# video_board.net
KiCad netlist of a schematic drawn in EAGLE
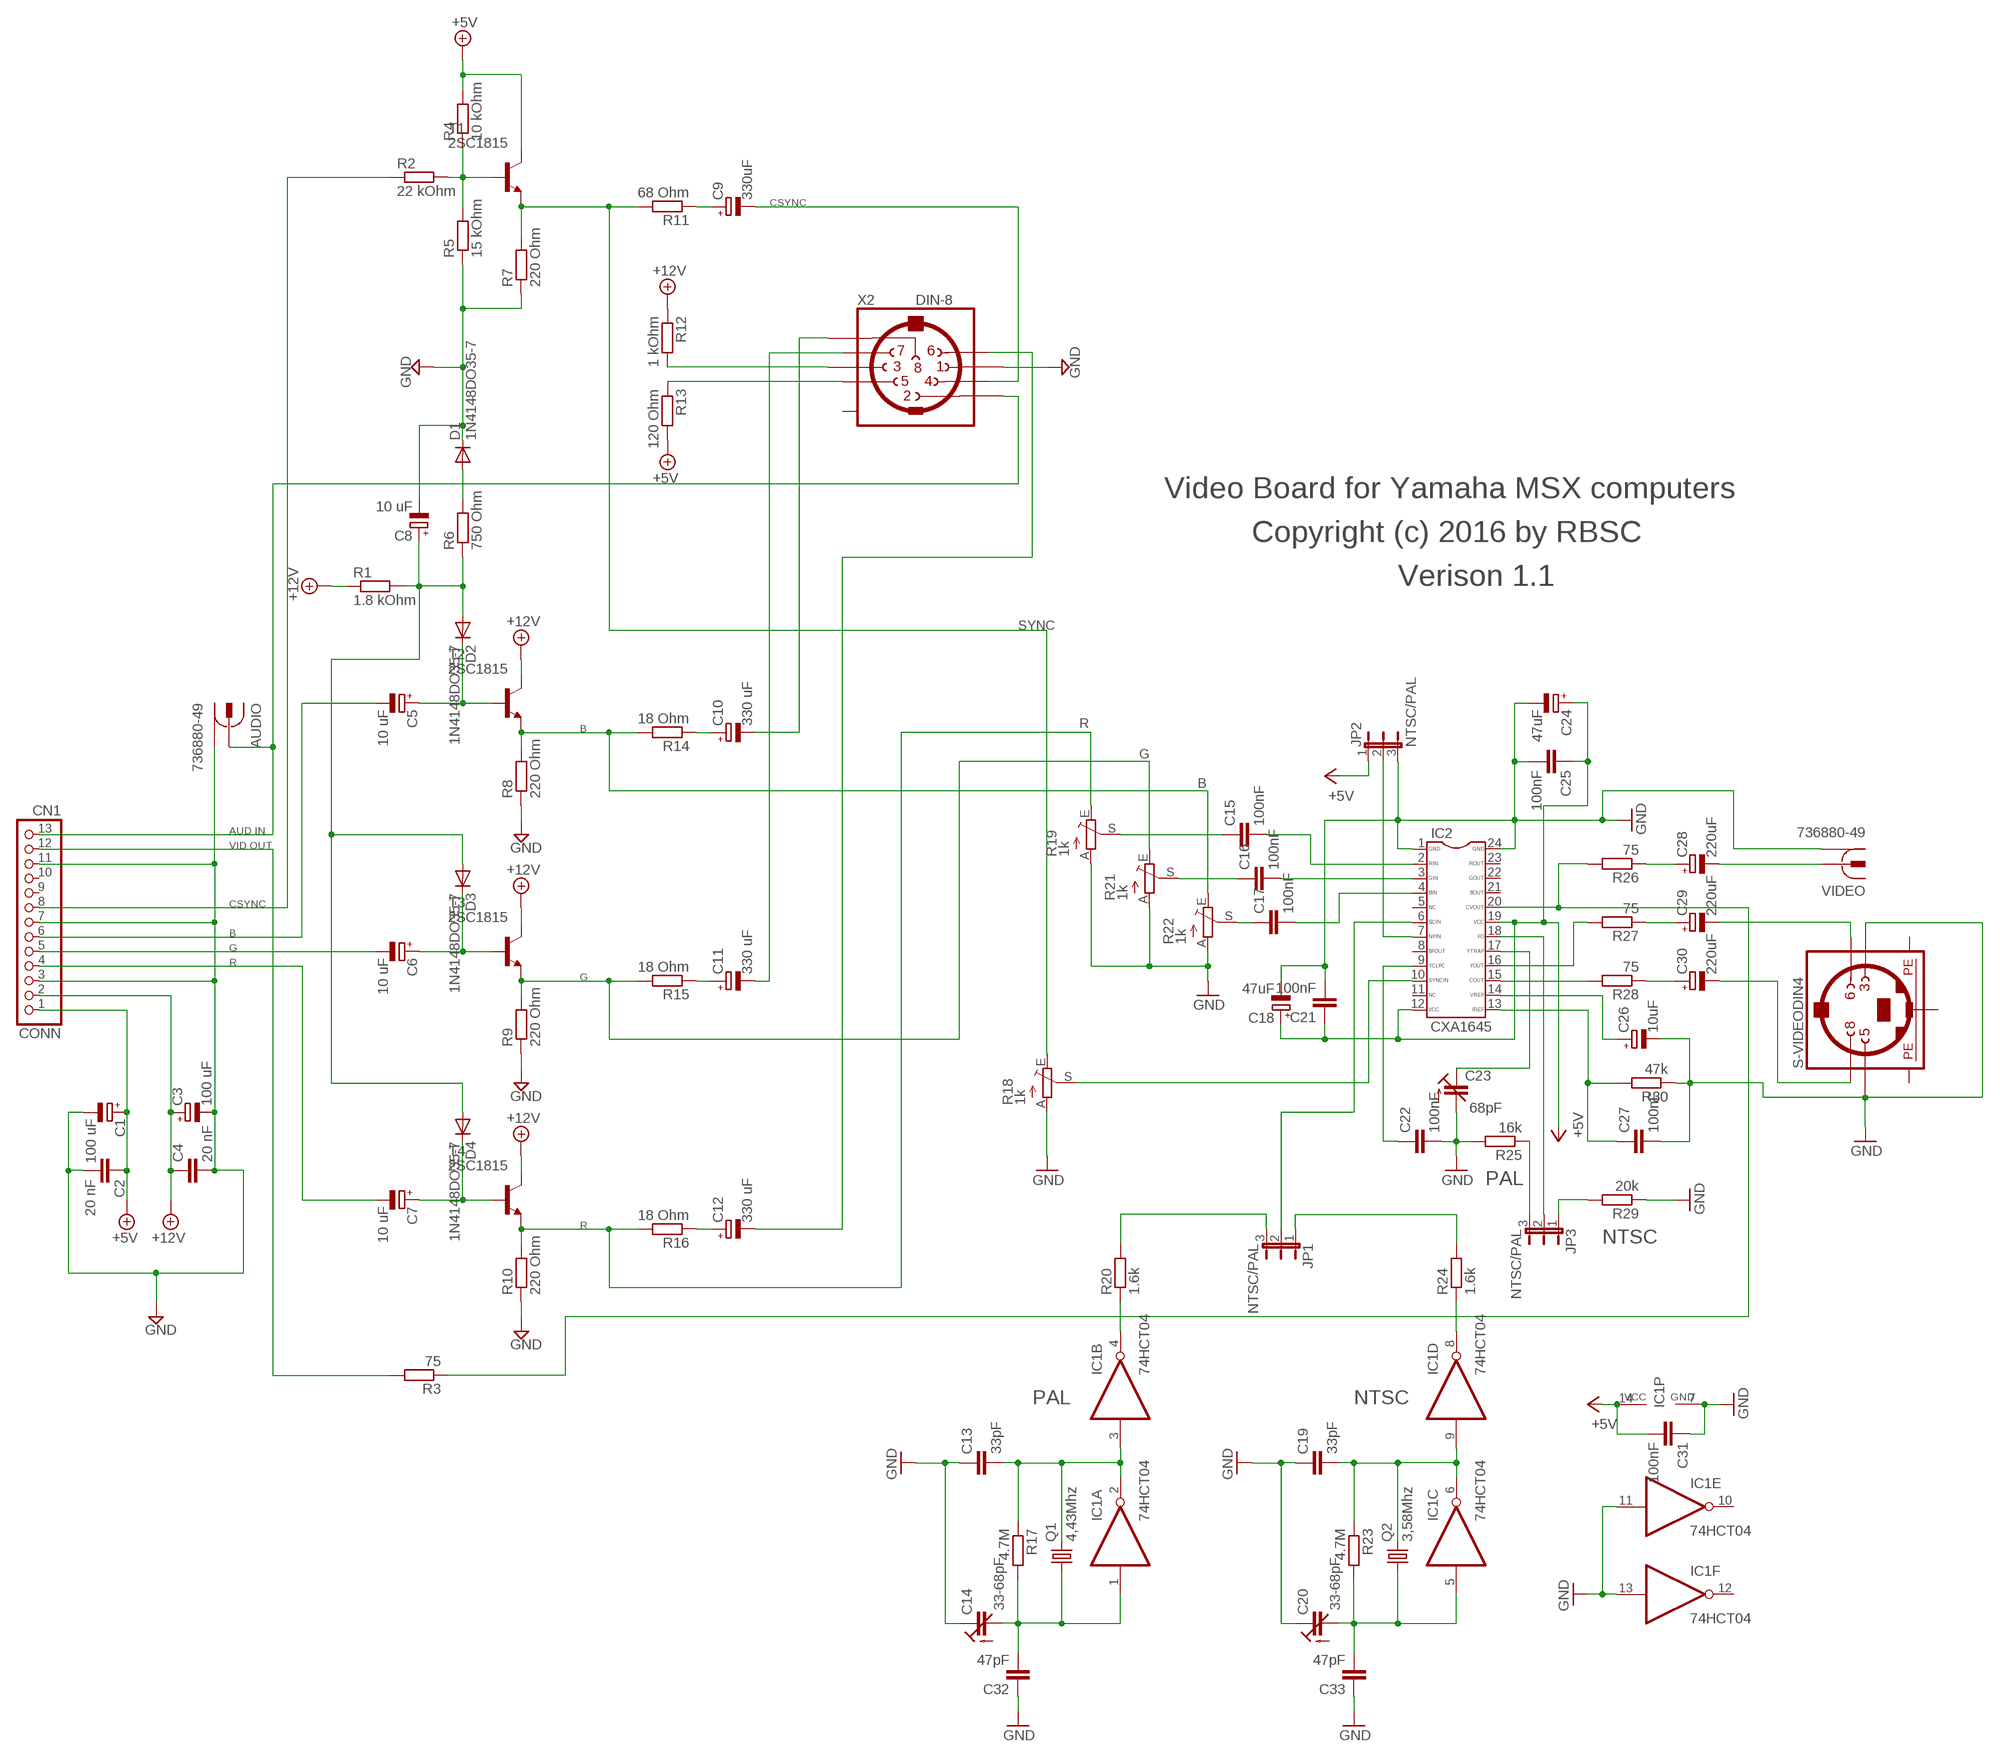
[diagram p0: schematic, sheet 1]

(export (version "E")
  (design (tool "Eeschema 10.0.6"))
  (components
    (comp (ref "AUDIO")
      (value "736880-49")
      (footprint "eagle-import:736880-49")
      (libsource (lib "eagle-import") (part "736880-49"))
    )
    (comp (ref "C1")
      (value "100 uF")
      (footprint "eagle-import:SMC_D")
      (libsource (lib "eagle-import") (part "CPOL-EUSMCD"))
    )
    (comp (ref "C2")
      (value "20 nF")
      (footprint "eagle-import:C0805")
      (libsource (lib "eagle-import") (part "C-EUC0805"))
    )
    (comp (ref "C3")
      (value "100 uF")
      (footprint "eagle-import:SMC_D")
      (libsource (lib "eagle-import") (part "CPOL-EUSMCD"))
    )
    (comp (ref "C4")
      (value "20 nF")
      (footprint "eagle-import:C0805")
      (libsource (lib "eagle-import") (part "C-EUC0805"))
    )
    (comp (ref "C5")
      (value "10 uF")
      (footprint "eagle-import:SMC_B")
      (libsource (lib "eagle-import") (part "CPOL-EUSMCB"))
    )
    (comp (ref "C6")
      (value "10 uF")
      (footprint "eagle-import:SMC_B")
      (libsource (lib "eagle-import") (part "CPOL-EUSMCB"))
    )
    (comp (ref "C7")
      (value "10 uF")
      (footprint "eagle-import:SMC_B")
      (libsource (lib "eagle-import") (part "CPOL-EUSMCB"))
    )
    (comp (ref "C8")
      (value "10 uF")
      (footprint "eagle-import:SMC_B")
      (libsource (lib "eagle-import") (part "CPOL-EUSMCB"))
    )
    (comp (ref "C9")
      (value "330uF")
      (footprint "eagle-import:SMC_D")
      (libsource (lib "eagle-import") (part "CPOL-EUSMCD"))
    )
    (comp (ref "C10")
      (value "330 uF")
      (footprint "eagle-import:SMC_D")
      (libsource (lib "eagle-import") (part "CPOL-EUSMCD"))
    )
    (comp (ref "C11")
      (value "330 uF")
      (footprint "eagle-import:SMC_D")
      (libsource (lib "eagle-import") (part "CPOL-EUSMCD"))
    )
    (comp (ref "C12")
      (value "330 uF")
      (footprint "eagle-import:SMC_D")
      (libsource (lib "eagle-import") (part "CPOL-EUSMCD"))
    )
    (comp (ref "C13")
      (value "33pF")
      (footprint "eagle-import:C0805")
      (libsource (lib "eagle-import") (part "C-EUC0805"))
    )
    (comp (ref "C14")
      (value "33-68pF")
      (footprint "eagle-import:CTRIMTZ03")
      (libsource (lib "eagle-import") (part "C-TRIMMTZ03"))
    )
    (comp (ref "C15")
      (value "100nF")
      (footprint "eagle-import:C0805")
      (libsource (lib "eagle-import") (part "C-EUC0805"))
    )
    (comp (ref "C16")
      (value "100nF")
      (footprint "eagle-import:C0805")
      (libsource (lib "eagle-import") (part "C-EUC0805"))
    )
    (comp (ref "C17")
      (value "100nF")
      (footprint "eagle-import:C0805")
      (libsource (lib "eagle-import") (part "C-EUC0805"))
    )
    (comp (ref "C18")
      (value "47uF")
      (footprint "eagle-import:SMC_B")
      (libsource (lib "eagle-import") (part "CPOL-EUSMCB"))
    )
    (comp (ref "C19")
      (value "33pF")
      (footprint "eagle-import:C0805")
      (libsource (lib "eagle-import") (part "C-EUC0805"))
    )
    (comp (ref "C20")
      (value "33-68pF")
      (footprint "eagle-import:CTRIMTZ03")
      (libsource (lib "eagle-import") (part "C-TRIMMTZ03"))
    )
    (comp (ref "C21")
      (value "100nF")
      (footprint "eagle-import:C0805")
      (libsource (lib "eagle-import") (part "C-EUC0805"))
    )
    (comp (ref "C22")
      (value "100nF")
      (footprint "eagle-import:C0805")
      (libsource (lib "eagle-import") (part "C-EUC0805"))
    )
    (comp (ref "C23")
      (value "68pF")
      (footprint "eagle-import:CTRIMTZ03")
      (libsource (lib "eagle-import") (part "C-TRIMMTZ03"))
    )
    (comp (ref "C24")
      (value "47uF")
      (footprint "eagle-import:SMC_B")
      (libsource (lib "eagle-import") (part "CPOL-EUSMCB"))
    )
    (comp (ref "C25")
      (value "100nF")
      (footprint "eagle-import:C0805")
      (libsource (lib "eagle-import") (part "C-EUC0805"))
    )
    (comp (ref "C26")
      (value "10uF")
      (footprint "eagle-import:SMC_B")
      (libsource (lib "eagle-import") (part "CPOL-EUSMCB"))
    )
    (comp (ref "C27")
      (value "100nF")
      (footprint "eagle-import:C0805")
      (libsource (lib "eagle-import") (part "C-EUC0805"))
    )
    (comp (ref "C28")
      (value "220uF")
      (footprint "eagle-import:SMC_D")
      (libsource (lib "eagle-import") (part "CPOL-EUSMCD"))
    )
    (comp (ref "C29")
      (value "220uF")
      (footprint "eagle-import:SMC_D")
      (libsource (lib "eagle-import") (part "CPOL-EUSMCD"))
    )
    (comp (ref "C30")
      (value "220uF")
      (footprint "eagle-import:SMC_D")
      (libsource (lib "eagle-import") (part "CPOL-EUSMCD"))
    )
    (comp (ref "C31")
      (value "100nF")
      (footprint "eagle-import:C0805")
      (libsource (lib "eagle-import") (part "C-EUC0805"))
    )
    (comp (ref "C32")
      (value "47pF")
      (footprint "eagle-import:C0805")
      (libsource (lib "eagle-import") (part "C-EUC0805"))
    )
    (comp (ref "C33")
      (value "47pF")
      (footprint "eagle-import:C0805")
      (libsource (lib "eagle-import") (part "C-EUC0805"))
    )
    (comp (ref "CONN")
      (value "CN1")
      (footprint "eagle-import:1X13")
      (libsource (lib "eagle-import") (part "PINHD-1X13"))
    )
    (comp (ref "D1")
      (value "1N4148DO35-7")
      (footprint "eagle-import:MINIMELF")
      (libsource (lib "eagle-import") (part "DIODE-MINIMELF"))
    )
    (comp (ref "D2")
      (value "1N4148DO35-7")
      (footprint "eagle-import:MINIMELF")
      (libsource (lib "eagle-import") (part "DIODE-MINIMELF"))
    )
    (comp (ref "D3")
      (value "1N4148DO35-7")
      (footprint "eagle-import:MINIMELF")
      (libsource (lib "eagle-import") (part "DIODE-MINIMELF"))
    )
    (comp (ref "D4")
      (value "1N4148DO35-7")
      (footprint "eagle-import:MINIMELF")
      (libsource (lib "eagle-import") (part "DIODE-MINIMELF"))
    )
    (comp (ref "IC1")
      (value "74HCT04")
      (footprint "eagle-import:SO14")
      (libsource (lib "eagle-import") (part "7404DHCT"))
    )
    (comp (ref "IC2")
      (value "CXA1645")
      (footprint "eagle-import:SOP24")
      (libsource (lib "eagle-import") (part "CXA1645"))
    )
    (comp (ref "JP1")
      (value "NTSC/PAL")
      (footprint "eagle-import:JP2")
      (libsource (lib "eagle-import") (part "JP2E"))
    )
    (comp (ref "JP2")
      (value "NTSC/PAL")
      (footprint "eagle-import:JP2")
      (libsource (lib "eagle-import") (part "JP2E"))
    )
    (comp (ref "JP3")
      (value "NTSC/PAL")
      (footprint "eagle-import:JP2")
      (libsource (lib "eagle-import") (part "JP2E"))
    )
    (comp (ref "Q1")
      (value "4,43Mhz")
      (footprint "eagle-import:HC49_S")
      (fields (field (name "MF") "MULTICOMP") (field (name "MPN") "HC49SM-3.6864-30-50-60-16-ATF"))
      (libsource (lib "eagle-import") (part "CRYSTALHC49S"))
    )
    (comp (ref "Q2")
      (value "3,58Mhz")
      (footprint "eagle-import:HC49_S")
      (fields (field (name "MF") "MULTICOMP") (field (name "MPN") "HC49SM-3.6864-30-50-60-16-ATF"))
      (libsource (lib "eagle-import") (part "CRYSTALHC49S"))
    )
    (comp (ref "R1")
      (value "1.8 kOhm")
      (footprint "eagle-import:R0805")
      (libsource (lib "eagle-import") (part "resistor_R-EU_R0805"))
    )
    (comp (ref "R2")
      (value "22 kOhm")
      (footprint "eagle-import:R0805")
      (libsource (lib "eagle-import") (part "resistor_R-EU_R0805"))
    )
    (comp (ref "R3")
      (value "75")
      (footprint "eagle-import:R0805")
      (libsource (lib "eagle-import") (part "R-EU_R0805"))
    )
    (comp (ref "R4")
      (value "10 kOhm")
      (footprint "eagle-import:R0805")
      (libsource (lib "eagle-import") (part "resistor_R-EU_R0805"))
    )
    (comp (ref "R5")
      (value "15 kOhm")
      (footprint "eagle-import:R0805")
      (libsource (lib "eagle-import") (part "resistor_R-EU_R0805"))
    )
    (comp (ref "R6")
      (value "750 Ohm")
      (footprint "eagle-import:R0805")
      (libsource (lib "eagle-import") (part "resistor_R-EU_R0805"))
    )
    (comp (ref "R7")
      (value "220 Ohm")
      (footprint "eagle-import:R0805")
      (libsource (lib "eagle-import") (part "resistor_R-EU_R0805"))
    )
    (comp (ref "R8")
      (value "220 Ohm")
      (footprint "eagle-import:R0805")
      (libsource (lib "eagle-import") (part "resistor_R-EU_R0805"))
    )
    (comp (ref "R9")
      (value "220 Ohm")
      (footprint "eagle-import:R0805")
      (libsource (lib "eagle-import") (part "resistor_R-EU_R0805"))
    )
    (comp (ref "R10")
      (value "220 Ohm")
      (footprint "eagle-import:R0805")
      (libsource (lib "eagle-import") (part "resistor_R-EU_R0805"))
    )
    (comp (ref "R11")
      (value "68 Ohm")
      (footprint "eagle-import:R0805")
      (libsource (lib "eagle-import") (part "resistor_R-EU_R0805"))
    )
    (comp (ref "R12")
      (value "1 kOhm")
      (footprint "eagle-import:R0805")
      (libsource (lib "eagle-import") (part "resistor_R-EU_R0805"))
    )
    (comp (ref "R13")
      (value "120 Ohm")
      (footprint "eagle-import:R0805")
      (libsource (lib "eagle-import") (part "resistor_R-EU_R0805"))
    )
    (comp (ref "R14")
      (value "18 Ohm")
      (footprint "eagle-import:R0805")
      (libsource (lib "eagle-import") (part "resistor_R-EU_R0805"))
    )
    (comp (ref "R15")
      (value "18 Ohm")
      (footprint "eagle-import:R0805")
      (libsource (lib "eagle-import") (part "resistor_R-EU_R0805"))
    )
    (comp (ref "R16")
      (value "18 Ohm")
      (footprint "eagle-import:R0805")
      (libsource (lib "eagle-import") (part "resistor_R-EU_R0805"))
    )
    (comp (ref "R17")
      (value "4.7M")
      (footprint "eagle-import:R0805")
      (libsource (lib "eagle-import") (part "R-EU_R0805"))
    )
    (comp (ref "R18")
      (value "1k")
      (footprint "eagle-import:CA6V")
      (libsource (lib "eagle-import") (part "TRIM_EU-CA6V"))
    )
    (comp (ref "R19")
      (value "1k")
      (footprint "eagle-import:CA6V")
      (libsource (lib "eagle-import") (part "TRIM_EU-CA6V"))
    )
    (comp (ref "R20")
      (value "1.6k")
      (footprint "eagle-import:R0805")
      (libsource (lib "eagle-import") (part "R-EU_R0805"))
    )
    (comp (ref "R21")
      (value "1k")
      (footprint "eagle-import:CA6V")
      (libsource (lib "eagle-import") (part "TRIM_EU-CA6V"))
    )
    (comp (ref "R22")
      (value "1k")
      (footprint "eagle-import:CA6V")
      (libsource (lib "eagle-import") (part "TRIM_EU-CA6V"))
    )
    (comp (ref "R23")
      (value "4.7M")
      (footprint "eagle-import:R0805")
      (libsource (lib "eagle-import") (part "R-EU_R0805"))
    )
    (comp (ref "R24")
      (value "1.6k")
      (footprint "eagle-import:R0805")
      (libsource (lib "eagle-import") (part "R-EU_R0805"))
    )
    (comp (ref "R25")
      (value "16k")
      (footprint "eagle-import:R0805")
      (libsource (lib "eagle-import") (part "R-EU_R0805"))
    )
    (comp (ref "R26")
      (value "75")
      (footprint "eagle-import:R0805")
      (libsource (lib "eagle-import") (part "R-EU_R0805"))
    )
    (comp (ref "R27")
      (value "75")
      (footprint "eagle-import:R0805")
      (libsource (lib "eagle-import") (part "R-EU_R0805"))
    )
    (comp (ref "R28")
      (value "75")
      (footprint "eagle-import:R0805")
      (libsource (lib "eagle-import") (part "R-EU_R0805"))
    )
    (comp (ref "R29")
      (value "20k")
      (footprint "eagle-import:R0805")
      (libsource (lib "eagle-import") (part "R-EU_R0805"))
    )
    (comp (ref "R30")
      (value "47k")
      (footprint "eagle-import:R0805")
      (libsource (lib "eagle-import") (part "R-EU_R0805"))
    )
    (comp (ref "S-VIDEO")
      (value "DIN4")
      (footprint "eagle-import:M_DIN4")
      (libsource (lib "eagle-import") (part "MINI_DIN_4"))
    )
    (comp (ref "T1")
      (value "2SC1815")
      (footprint "eagle-import:TO92-ECB")
      (libsource (lib "eagle-import") (part "2SC1815"))
    )
    (comp (ref "T2")
      (value "2SC1815")
      (footprint "eagle-import:TO92-ECB")
      (libsource (lib "eagle-import") (part "2SC1815"))
    )
    (comp (ref "T3")
      (value "2SC1815")
      (footprint "eagle-import:TO92-ECB")
      (libsource (lib "eagle-import") (part "2SC1815"))
    )
    (comp (ref "T4")
      (value "2SC1815")
      (footprint "eagle-import:TO92-ECB")
      (libsource (lib "eagle-import") (part "2SC1815"))
    )
    (comp (ref "VIDEO")
      (value "736880-49")
      (footprint "eagle-import:736880-49")
      (libsource (lib "eagle-import") (part "736880-49"))
    )
    (comp (ref "X2")
      (value "DIN-8")
      (footprint "eagle-import:DIN8")
      (libsource (lib "eagle-import") (part "DIN-8"))
    )
  )
  (nets
    (net (code "1") (name "+5V") (class "Default")
      (node (ref "C1") (pin "+") (pinfunction "+_+") (pintype "passive"))
      (node (ref "C18") (pin "+") (pinfunction "+_+") (pintype "passive"))
      (node (ref "C2") (pin "1") (pinfunction "1_1") (pintype "passive"))
      (node (ref "C21") (pin "1") (pinfunction "1_1") (pintype "passive"))
      (node (ref "C24") (pin "+") (pinfunction "+_+") (pintype "passive"))
      (node (ref "C25") (pin "1") (pinfunction "1_1") (pintype "passive"))
      (node (ref "C31") (pin "2") (pinfunction "2_2") (pintype "passive"))
      (node (ref "CONN") (pin "1") (pinfunction "1_1") (pintype "passive"))
      (node (ref "IC1") (pin "14") (pinfunction "VCC_14") (pintype "power_in"))
      (node (ref "IC2") (pin "12") (pinfunction "12_12") (pintype "passive"))
      (node (ref "IC2") (pin "19") (pinfunction "19_19") (pintype "passive"))
      (node (ref "JP2") (pin "1") (pinfunction "1_1") (pintype "passive"))
      (node (ref "R13") (pin "2") (pinfunction "2_2") (pintype "passive"))
      (node (ref "R4") (pin "2") (pinfunction "2_2") (pintype "passive"))
      (node (ref "T1") (pin "C") (pinfunction "C_C") (pintype "passive"))
    )
    (net (code "2") (name "+12V") (class "Default")
      (node (ref "C3") (pin "+") (pinfunction "+_+") (pintype "passive"))
      (node (ref "C4") (pin "1") (pinfunction "1_1") (pintype "passive"))
      (node (ref "CONN") (pin "2") (pinfunction "2_2") (pintype "passive"))
      (node (ref "R1") (pin "1") (pinfunction "1_1") (pintype "passive"))
      (node (ref "R12") (pin "1") (pinfunction "1_1") (pintype "passive"))
      (node (ref "T2") (pin "C") (pinfunction "C_C") (pintype "passive"))
      (node (ref "T3") (pin "C") (pinfunction "C_C") (pintype "passive"))
      (node (ref "T4") (pin "C") (pinfunction "C_C") (pintype "passive"))
    )
    (net (code "3") (name "/PE1") (class "Default")
      (node (ref "S-VIDEO") (pin "SH1") (pinfunction "PE1_SH1") (pintype "power_in"))
    )
    (net (code "4") (name "/PE2") (class "Default")
      (node (ref "S-VIDEO") (pin "SH2") (pinfunction "PE2_SH2") (pintype "power_in"))
    )
    (net (code "5") (name "/PE3") (class "Default")
      (node (ref "S-VIDEO") (pin "SH3") (pinfunction "PE3_SH3") (pintype "power_in"))
    )
    (net (code "6") (name "GND") (class "Default")
      (node (ref "AUDIO") (pin "1") (pinfunction "1_1") (pintype "passive"))
      (node (ref "AUDIO") (pin "1@1") (pinfunction "1_1@1") (pintype "passive"))
      (node (ref "AUDIO") (pin "1@2") (pinfunction "1_1@2") (pintype "passive"))
      (node (ref "C1") (pin "-") (pinfunction "-_-") (pintype "passive"))
      (node (ref "C13") (pin "1") (pinfunction "1_1") (pintype "passive"))
      (node (ref "C14") (pin "1") (pinfunction "E_1") (pintype "passive"))
      (node (ref "C18") (pin "-") (pinfunction "-_-") (pintype "passive"))
      (node (ref "C19") (pin "1") (pinfunction "1_1") (pintype "passive"))
      (node (ref "C2") (pin "2") (pinfunction "2_2") (pintype "passive"))
      (node (ref "C20") (pin "1") (pinfunction "E_1") (pintype "passive"))
      (node (ref "C21") (pin "2") (pinfunction "2_2") (pintype "passive"))
      (node (ref "C22") (pin "2") (pinfunction "2_2") (pintype "passive"))
      (node (ref "C23") (pin "2") (pinfunction "A_2") (pintype "passive"))
      (node (ref "C24") (pin "-") (pinfunction "-_-") (pintype "passive"))
      (node (ref "C25") (pin "2") (pinfunction "2_2") (pintype "passive"))
      (node (ref "C26") (pin "-") (pinfunction "-_-") (pintype "passive"))
      (node (ref "C27") (pin "2") (pinfunction "2_2") (pintype "passive"))
      (node (ref "C3") (pin "-") (pinfunction "-_-") (pintype "passive"))
      (node (ref "C31") (pin "1") (pinfunction "1_1") (pintype "passive"))
      (node (ref "C32") (pin "1") (pinfunction "1_1") (pintype "passive"))
      (node (ref "C33") (pin "1") (pinfunction "1_1") (pintype "passive"))
      (node (ref "C4") (pin "2") (pinfunction "2_2") (pintype "passive"))
      (node (ref "C8") (pin "-") (pinfunction "-_-") (pintype "passive"))
      (node (ref "CONN") (pin "11") (pinfunction "11_11") (pintype "passive"))
      (node (ref "CONN") (pin "3") (pinfunction "3_3") (pintype "passive"))
      (node (ref "CONN") (pin "7") (pinfunction "7_7") (pintype "passive"))
      (node (ref "D1") (pin "C") (pinfunction "C_C") (pintype "passive"))
      (node (ref "IC1") (pin "11") (pinfunction "I_11") (pintype "input"))
      (node (ref "IC1") (pin "13") (pinfunction "I_13") (pintype "input"))
      (node (ref "IC1") (pin "7") (pinfunction "GND_7") (pintype "power_in"))
      (node (ref "IC2") (pin "1") (pinfunction "1_1") (pintype "passive"))
      (node (ref "IC2") (pin "24") (pinfunction "24_24") (pintype "passive"))
      (node (ref "JP2") (pin "3") (pinfunction "3_3") (pintype "passive"))
      (node (ref "R10") (pin "1") (pinfunction "1_1") (pintype "passive"))
      (node (ref "R18") (pin "A") (pinfunction "A_A") (pintype "passive"))
      (node (ref "R19") (pin "A") (pinfunction "A_A") (pintype "passive"))
      (node (ref "R21") (pin "A") (pinfunction "A_A") (pintype "passive"))
      (node (ref "R22") (pin "A") (pinfunction "A_A") (pintype "passive"))
      (node (ref "R25") (pin "2") (pinfunction "2_2") (pintype "passive"))
      (node (ref "R29") (pin "1") (pinfunction "1_1") (pintype "passive"))
      (node (ref "R30") (pin "1") (pinfunction "1_1") (pintype "passive"))
      (node (ref "R5") (pin "1") (pinfunction "1_1") (pintype "passive"))
      (node (ref "R7") (pin "1") (pinfunction "1_1") (pintype "passive"))
      (node (ref "R8") (pin "1") (pinfunction "1_1") (pintype "passive"))
      (node (ref "R9") (pin "1") (pinfunction "1_1") (pintype "passive"))
      (node (ref "S-VIDEO") (pin "3") (pinfunction "3_3") (pintype "passive"))
      (node (ref "S-VIDEO") (pin "5") (pinfunction "5_5") (pintype "passive"))
      (node (ref "VIDEO") (pin "1") (pinfunction "1_1") (pintype "passive"))
      (node (ref "VIDEO") (pin "1@1") (pinfunction "1_1@1") (pintype "passive"))
      (node (ref "VIDEO") (pin "1@2") (pinfunction "1_1@2") (pintype "passive"))
      (node (ref "X2") (pin "1") (pinfunction "1_1") (pintype "passive"))
    )
    (net (code "7") (name "Net-(AUDIO-Pad2)") (class "Default")
      (node (ref "AUDIO") (pin "2") (pinfunction "2_2") (pintype "passive"))
      (node (ref "CONN") (pin "13") (pinfunction "13_13") (pintype "passive"))
      (node (ref "X2") (pin "2") (pinfunction "2_2") (pintype "passive"))
    )
    (net (code "8") (name "Net-(C5-Pad+)") (class "Default")
      (node (ref "C5") (pin "+") (pinfunction "+_+") (pintype "passive"))
      (node (ref "D2") (pin "C") (pinfunction "C_C") (pintype "passive"))
      (node (ref "T2") (pin "B") (pinfunction "B_B") (pintype "passive"))
    )
    (net (code "9") (name "Net-(C5-Pad-)") (class "Default")
      (node (ref "C5") (pin "-") (pinfunction "-_-") (pintype "passive"))
      (node (ref "CONN") (pin "6") (pinfunction "6_6") (pintype "passive"))
    )
    (net (code "10") (name "Net-(C6-Pad+)") (class "Default")
      (node (ref "C6") (pin "+") (pinfunction "+_+") (pintype "passive"))
      (node (ref "D3") (pin "C") (pinfunction "C_C") (pintype "passive"))
      (node (ref "T3") (pin "B") (pinfunction "B_B") (pintype "passive"))
    )
    (net (code "11") (name "Net-(C6-Pad-)") (class "Default")
      (node (ref "C6") (pin "-") (pinfunction "-_-") (pintype "passive"))
      (node (ref "CONN") (pin "5") (pinfunction "5_5") (pintype "passive"))
    )
    (net (code "12") (name "Net-(C7-Pad+)") (class "Default")
      (node (ref "C7") (pin "+") (pinfunction "+_+") (pintype "passive"))
      (node (ref "D4") (pin "C") (pinfunction "C_C") (pintype "passive"))
      (node (ref "T4") (pin "B") (pinfunction "B_B") (pintype "passive"))
    )
    (net (code "13") (name "Net-(C7-Pad-)") (class "Default")
      (node (ref "C7") (pin "-") (pinfunction "-_-") (pintype "passive"))
      (node (ref "CONN") (pin "4") (pinfunction "4_4") (pintype "passive"))
    )
    (net (code "14") (name "Net-(C8-Pad+)") (class "Default")
      (node (ref "C8") (pin "+") (pinfunction "+_+") (pintype "passive"))
      (node (ref "D2") (pin "A") (pinfunction "A_A") (pintype "passive"))
      (node (ref "D3") (pin "A") (pinfunction "A_A") (pintype "passive"))
      (node (ref "D4") (pin "A") (pinfunction "A_A") (pintype "passive"))
      (node (ref "R1") (pin "2") (pinfunction "2_2") (pintype "passive"))
      (node (ref "R6") (pin "1") (pinfunction "1_1") (pintype "passive"))
    )
    (net (code "15") (name "Net-(C9-Pad+)") (class "Default")
      (node (ref "C9") (pin "+") (pinfunction "+_+") (pintype "passive"))
      (node (ref "R11") (pin "1") (pinfunction "1_1") (pintype "passive"))
    )
    (net (code "16") (name "Net-(C9-Pad-)") (class "Default")
      (node (ref "C9") (pin "-") (pinfunction "-_-") (pintype "passive"))
      (node (ref "X2") (pin "4") (pinfunction "4_4") (pintype "passive"))
    )
    (net (code "17") (name "Net-(C10-Pad+)") (class "Default")
      (node (ref "C10") (pin "+") (pinfunction "+_+") (pintype "passive"))
      (node (ref "R14") (pin "1") (pinfunction "1_1") (pintype "passive"))
    )
    (net (code "18") (name "Net-(C10-Pad-)") (class "Default")
      (node (ref "C10") (pin "-") (pinfunction "-_-") (pintype "passive"))
      (node (ref "X2") (pin "8") (pinfunction "8_8") (pintype "passive"))
    )
    (net (code "19") (name "Net-(C11-Pad+)") (class "Default")
      (node (ref "C11") (pin "+") (pinfunction "+_+") (pintype "passive"))
      (node (ref "R15") (pin "1") (pinfunction "1_1") (pintype "passive"))
    )
    (net (code "20") (name "Net-(C11-Pad-)") (class "Default")
      (node (ref "C11") (pin "-") (pinfunction "-_-") (pintype "passive"))
      (node (ref "X2") (pin "7") (pinfunction "7_7") (pintype "passive"))
    )
    (net (code "21") (name "Net-(C12-Pad+)") (class "Default")
      (node (ref "C12") (pin "+") (pinfunction "+_+") (pintype "passive"))
      (node (ref "R16") (pin "1") (pinfunction "1_1") (pintype "passive"))
    )
    (net (code "22") (name "Net-(C12-Pad-)") (class "Default")
      (node (ref "C12") (pin "-") (pinfunction "-_-") (pintype "passive"))
      (node (ref "X2") (pin "6") (pinfunction "6_6") (pintype "passive"))
    )
    (net (code "23") (name "Net-(C14-A)") (class "Default")
      (node (ref "C14") (pin "2") (pinfunction "A_2") (pintype "passive"))
      (node (ref "C32") (pin "2") (pinfunction "2_2") (pintype "passive"))
      (node (ref "IC1") (pin "1") (pinfunction "I_1") (pintype "input"))
      (node (ref "Q1") (pin "1") (pinfunction "1_1") (pintype "passive"))
      (node (ref "R17") (pin "2") (pinfunction "2_2") (pintype "passive"))
    )
    (net (code "24") (name "Net-(C15-Pad1)") (class "Default")
      (node (ref "C15") (pin "1") (pinfunction "1_1") (pintype "passive"))
      (node (ref "R19") (pin "S") (pinfunction "S_S") (pintype "passive"))
    )
    (net (code "25") (name "Net-(C15-Pad2)") (class "Default")
      (node (ref "C15") (pin "2") (pinfunction "2_2") (pintype "passive"))
      (node (ref "IC2") (pin "2") (pinfunction "2_2") (pintype "passive"))
    )
    (net (code "26") (name "Net-(C16-Pad1)") (class "Default")
      (node (ref "C16") (pin "1") (pinfunction "1_1") (pintype "passive"))
      (node (ref "R21") (pin "S") (pinfunction "S_S") (pintype "passive"))
    )
    (net (code "27") (name "Net-(C16-Pad2)") (class "Default")
      (node (ref "C16") (pin "2") (pinfunction "2_2") (pintype "passive"))
      (node (ref "IC2") (pin "3") (pinfunction "3_3") (pintype "passive"))
    )
    (net (code "28") (name "Net-(C17-Pad1)") (class "Default")
      (node (ref "C17") (pin "1") (pinfunction "1_1") (pintype "passive"))
      (node (ref "R22") (pin "S") (pinfunction "S_S") (pintype "passive"))
    )
    (net (code "29") (name "Net-(C17-Pad2)") (class "Default")
      (node (ref "C17") (pin "2") (pinfunction "2_2") (pintype "passive"))
      (node (ref "IC2") (pin "4") (pinfunction "4_4") (pintype "passive"))
    )
    (net (code "30") (name "Net-(C20-A)") (class "Default")
      (node (ref "C20") (pin "2") (pinfunction "A_2") (pintype "passive"))
      (node (ref "C33") (pin "2") (pinfunction "2_2") (pintype "passive"))
      (node (ref "IC1") (pin "5") (pinfunction "I_5") (pintype "input"))
      (node (ref "Q2") (pin "1") (pinfunction "1_1") (pintype "passive"))
      (node (ref "R23") (pin "2") (pinfunction "2_2") (pintype "passive"))
    )
    (net (code "31") (name "Net-(C22-Pad1)") (class "Default")
      (node (ref "C22") (pin "1") (pinfunction "1_1") (pintype "passive"))
      (node (ref "IC2") (pin "9") (pinfunction "9_9") (pintype "passive"))
    )
    (net (code "32") (name "Net-(C23-E)") (class "Default")
      (node (ref "C23") (pin "1") (pinfunction "E_1") (pintype "passive"))
      (node (ref "IC2") (pin "17") (pinfunction "17_17") (pintype "passive"))
    )
    (net (code "33") (name "Net-(C26-Pad+)") (class "Default")
      (node (ref "C26") (pin "+") (pinfunction "+_+") (pintype "passive"))
      (node (ref "IC2") (pin "14") (pinfunction "14_14") (pintype "passive"))
    )
    (net (code "34") (name "Net-(C27-Pad1)") (class "Default")
      (node (ref "C27") (pin "1") (pinfunction "1_1") (pintype "passive"))
      (node (ref "IC2") (pin "13") (pinfunction "13_13") (pintype "passive"))
      (node (ref "R30") (pin "2") (pinfunction "2_2") (pintype "passive"))
    )
    (net (code "35") (name "Net-(C28-Pad+)") (class "Default")
      (node (ref "C28") (pin "+") (pinfunction "+_+") (pintype "passive"))
      (node (ref "R26") (pin "1") (pinfunction "1_1") (pintype "passive"))
    )
    (net (code "36") (name "Net-(C28-Pad-)") (class "Default")
      (node (ref "C28") (pin "-") (pinfunction "-_-") (pintype "passive"))
      (node (ref "VIDEO") (pin "2") (pinfunction "2_2") (pintype "passive"))
    )
    (net (code "37") (name "Net-(C29-Pad+)") (class "Default")
      (node (ref "C29") (pin "+") (pinfunction "+_+") (pintype "passive"))
      (node (ref "R27") (pin "1") (pinfunction "1_1") (pintype "passive"))
    )
    (net (code "38") (name "Net-(C29-Pad-)") (class "Default")
      (node (ref "C29") (pin "-") (pinfunction "-_-") (pintype "passive"))
      (node (ref "S-VIDEO") (pin "6") (pinfunction "6_6") (pintype "passive"))
    )
    (net (code "39") (name "Net-(C30-Pad+)") (class "Default")
      (node (ref "C30") (pin "+") (pinfunction "+_+") (pintype "passive"))
      (node (ref "R28") (pin "1") (pinfunction "1_1") (pintype "passive"))
    )
    (net (code "40") (name "Net-(C30-Pad-)") (class "Default")
      (node (ref "C30") (pin "-") (pinfunction "-_-") (pintype "passive"))
      (node (ref "S-VIDEO") (pin "8") (pinfunction "8_8") (pintype "passive"))
    )
    (net (code "41") (name "Net-(CONN-Pad8)") (class "Default")
      (node (ref "CONN") (pin "8") (pinfunction "8_8") (pintype "passive"))
      (node (ref "R2") (pin "1") (pinfunction "1_1") (pintype "passive"))
    )
    (net (code "42") (name "Net-(CONN-Pad12)") (class "Default")
      (node (ref "CONN") (pin "12") (pinfunction "12_12") (pintype "passive"))
      (node (ref "R3") (pin "2") (pinfunction "2_2") (pintype "passive"))
    )
    (net (code "43") (name "Net-(D1-PadA)") (class "Default")
      (node (ref "D1") (pin "A") (pinfunction "A_A") (pintype "passive"))
      (node (ref "R6") (pin "2") (pinfunction "2_2") (pintype "passive"))
    )
    (net (code "44") (name "Net-(IC1A-O)") (class "Default")
      (node (ref "C13") (pin "2") (pinfunction "2_2") (pintype "passive"))
      (node (ref "IC1") (pin "2") (pinfunction "O_2") (pintype "output"))
      (node (ref "IC1") (pin "3") (pinfunction "I_3") (pintype "input"))
      (node (ref "Q1") (pin "2") (pinfunction "2_2") (pintype "passive"))
      (node (ref "R17") (pin "1") (pinfunction "1_1") (pintype "passive"))
    )
    (net (code "45") (name "Net-(IC1B-O)") (class "Default")
      (node (ref "IC1") (pin "4") (pinfunction "O_4") (pintype "output"))
      (node (ref "R20") (pin "1") (pinfunction "1_1") (pintype "passive"))
    )
    (net (code "46") (name "Net-(IC1C-O)") (class "Default")
      (node (ref "C19") (pin "2") (pinfunction "2_2") (pintype "passive"))
      (node (ref "IC1") (pin "6") (pinfunction "O_6") (pintype "output"))
      (node (ref "IC1") (pin "9") (pinfunction "I_9") (pintype "input"))
      (node (ref "Q2") (pin "2") (pinfunction "2_2") (pintype "passive"))
      (node (ref "R23") (pin "1") (pinfunction "1_1") (pintype "passive"))
    )
    (net (code "47") (name "Net-(IC1D-O)") (class "Default")
      (node (ref "IC1") (pin "8") (pinfunction "O_8") (pintype "output"))
      (node (ref "R24") (pin "1") (pinfunction "1_1") (pintype "passive"))
    )
    (net (code "48") (name "Net-(IC2-Pad6)") (class "Default")
      (node (ref "IC2") (pin "6") (pinfunction "6_6") (pintype "passive"))
      (node (ref "JP1") (pin "2") (pinfunction "2_2") (pintype "passive"))
    )
    (net (code "49") (name "Net-(IC2-Pad7)") (class "Default")
      (node (ref "IC2") (pin "7") (pinfunction "7_7") (pintype "passive"))
      (node (ref "JP2") (pin "2") (pinfunction "2_2") (pintype "passive"))
    )
    (net (code "50") (name "Net-(IC2-Pad10)") (class "Default")
      (node (ref "IC2") (pin "10") (pinfunction "10_10") (pintype "passive"))
      (node (ref "R18") (pin "S") (pinfunction "S_S") (pintype "passive"))
    )
    (net (code "51") (name "Net-(IC2-Pad15)") (class "Default")
      (node (ref "IC2") (pin "15") (pinfunction "15_15") (pintype "passive"))
      (node (ref "R28") (pin "2") (pinfunction "2_2") (pintype "passive"))
    )
    (net (code "52") (name "Net-(IC2-Pad16)") (class "Default")
      (node (ref "IC2") (pin "16") (pinfunction "16_16") (pintype "passive"))
      (node (ref "R27") (pin "2") (pinfunction "2_2") (pintype "passive"))
    )
    (net (code "53") (name "Net-(IC2-Pad18)") (class "Default")
      (node (ref "IC2") (pin "18") (pinfunction "18_18") (pintype "passive"))
      (node (ref "JP3") (pin "2") (pinfunction "2_2") (pintype "passive"))
    )
    (net (code "54") (name "Net-(IC2-Pad20)") (class "Default")
      (node (ref "IC2") (pin "20") (pinfunction "20_20") (pintype "passive"))
      (node (ref "R26") (pin "2") (pinfunction "2_2") (pintype "passive"))
      (node (ref "R3") (pin "1") (pinfunction "1_1") (pintype "passive"))
    )
    (net (code "55") (name "Net-(JP1-Pad1)") (class "Default")
      (node (ref "JP1") (pin "1") (pinfunction "1_1") (pintype "passive"))
      (node (ref "R24") (pin "2") (pinfunction "2_2") (pintype "passive"))
    )
    (net (code "56") (name "Net-(JP1-Pad3)") (class "Default")
      (node (ref "JP1") (pin "3") (pinfunction "3_3") (pintype "passive"))
      (node (ref "R20") (pin "2") (pinfunction "2_2") (pintype "passive"))
    )
    (net (code "57") (name "Net-(JP3-Pad1)") (class "Default")
      (node (ref "JP3") (pin "1") (pinfunction "1_1") (pintype "passive"))
      (node (ref "R29") (pin "2") (pinfunction "2_2") (pintype "passive"))
    )
    (net (code "58") (name "Net-(JP3-Pad3)") (class "Default")
      (node (ref "JP3") (pin "3") (pinfunction "3_3") (pintype "passive"))
      (node (ref "R25") (pin "1") (pinfunction "1_1") (pintype "passive"))
    )
    (net (code "59") (name "Net-(R2-Pad2)") (class "Default")
      (node (ref "R2") (pin "2") (pinfunction "2_2") (pintype "passive"))
      (node (ref "R4") (pin "1") (pinfunction "1_1") (pintype "passive"))
      (node (ref "R5") (pin "2") (pinfunction "2_2") (pintype "passive"))
      (node (ref "T1") (pin "B") (pinfunction "B_B") (pintype "passive"))
    )
    (net (code "60") (name "Net-(R10-Pad2)") (class "Default")
      (node (ref "R10") (pin "2") (pinfunction "2_2") (pintype "passive"))
      (node (ref "R16") (pin "2") (pinfunction "2_2") (pintype "passive"))
      (node (ref "R19") (pin "E") (pinfunction "E_E") (pintype "passive"))
      (node (ref "T4") (pin "E") (pinfunction "E_E") (pintype "passive"))
    )
    (net (code "61") (name "Net-(R11-Pad2)") (class "Default")
      (node (ref "R11") (pin "2") (pinfunction "2_2") (pintype "passive"))
      (node (ref "R18") (pin "E") (pinfunction "E_E") (pintype "passive"))
      (node (ref "R7") (pin "2") (pinfunction "2_2") (pintype "passive"))
      (node (ref "T1") (pin "E") (pinfunction "E_E") (pintype "passive"))
    )
    (net (code "62") (name "Net-(R12-Pad2)") (class "Default")
      (node (ref "R12") (pin "2") (pinfunction "2_2") (pintype "passive"))
      (node (ref "X2") (pin "3") (pinfunction "3_3") (pintype "passive"))
    )
    (net (code "63") (name "Net-(R13-Pad1)") (class "Default")
      (node (ref "R13") (pin "1") (pinfunction "1_1") (pintype "passive"))
      (node (ref "X2") (pin "5") (pinfunction "5_5") (pintype "passive"))
    )
    (net (code "64") (name "Net-(R14-Pad2)") (class "Default")
      (node (ref "R14") (pin "2") (pinfunction "2_2") (pintype "passive"))
      (node (ref "R22") (pin "E") (pinfunction "E_E") (pintype "passive"))
      (node (ref "R8") (pin "2") (pinfunction "2_2") (pintype "passive"))
      (node (ref "T2") (pin "E") (pinfunction "E_E") (pintype "passive"))
    )
    (net (code "65") (name "Net-(R15-Pad2)") (class "Default")
      (node (ref "R15") (pin "2") (pinfunction "2_2") (pintype "passive"))
      (node (ref "R21") (pin "E") (pinfunction "E_E") (pintype "passive"))
      (node (ref "R9") (pin "2") (pinfunction "2_2") (pintype "passive"))
      (node (ref "T3") (pin "E") (pinfunction "E_E") (pintype "passive"))
    )
    (net (code "66") (name "unconnected-(CONN-Pad9)") (class "Default")
      (node (ref "CONN") (pin "9") (pinfunction "9_9") (pintype "passive"))
    )
    (net (code "67") (name "unconnected-(CONN-Pad10)") (class "Default")
      (node (ref "CONN") (pin "10") (pinfunction "10_10") (pintype "passive"))
    )
    (net (code "68") (name "unconnected-(IC1E-O-Pad10)") (class "Default")
      (node (ref "IC1") (pin "10") (pinfunction "O_10") (pintype "output"))
    )
    (net (code "69") (name "unconnected-(IC1F-O-Pad12)") (class "Default")
      (node (ref "IC1") (pin "12") (pinfunction "O_12") (pintype "output"))
    )
    (net (code "70") (name "unconnected-(IC2-Pad5)") (class "Default")
      (node (ref "IC2") (pin "5") (pinfunction "5_5") (pintype "passive"))
    )
    (net (code "71") (name "unconnected-(IC2-Pad8)") (class "Default")
      (node (ref "IC2") (pin "8") (pinfunction "8_8") (pintype "passive"))
    )
    (net (code "72") (name "unconnected-(IC2-Pad11)") (class "Default")
      (node (ref "IC2") (pin "11") (pinfunction "11_11") (pintype "passive"))
    )
    (net (code "73") (name "unconnected-(IC2-Pad21)") (class "Default")
      (node (ref "IC2") (pin "21") (pinfunction "21_21") (pintype "passive"))
    )
    (net (code "74") (name "unconnected-(IC2-Pad22)") (class "Default")
      (node (ref "IC2") (pin "22") (pinfunction "22_22") (pintype "passive"))
    )
    (net (code "75") (name "unconnected-(IC2-Pad23)") (class "Default")
      (node (ref "IC2") (pin "23") (pinfunction "23_23") (pintype "passive"))
    )
    (net (code "76") (name "unconnected-(X2-PadGND)") (class "Default")
      (node (ref "X2") (pin "GND") (pinfunction "GND_GND") (pintype "no_connect"))
    )
  )
)
